# GPduino.net
KiCad netlist of a schematic drawn in EAGLE
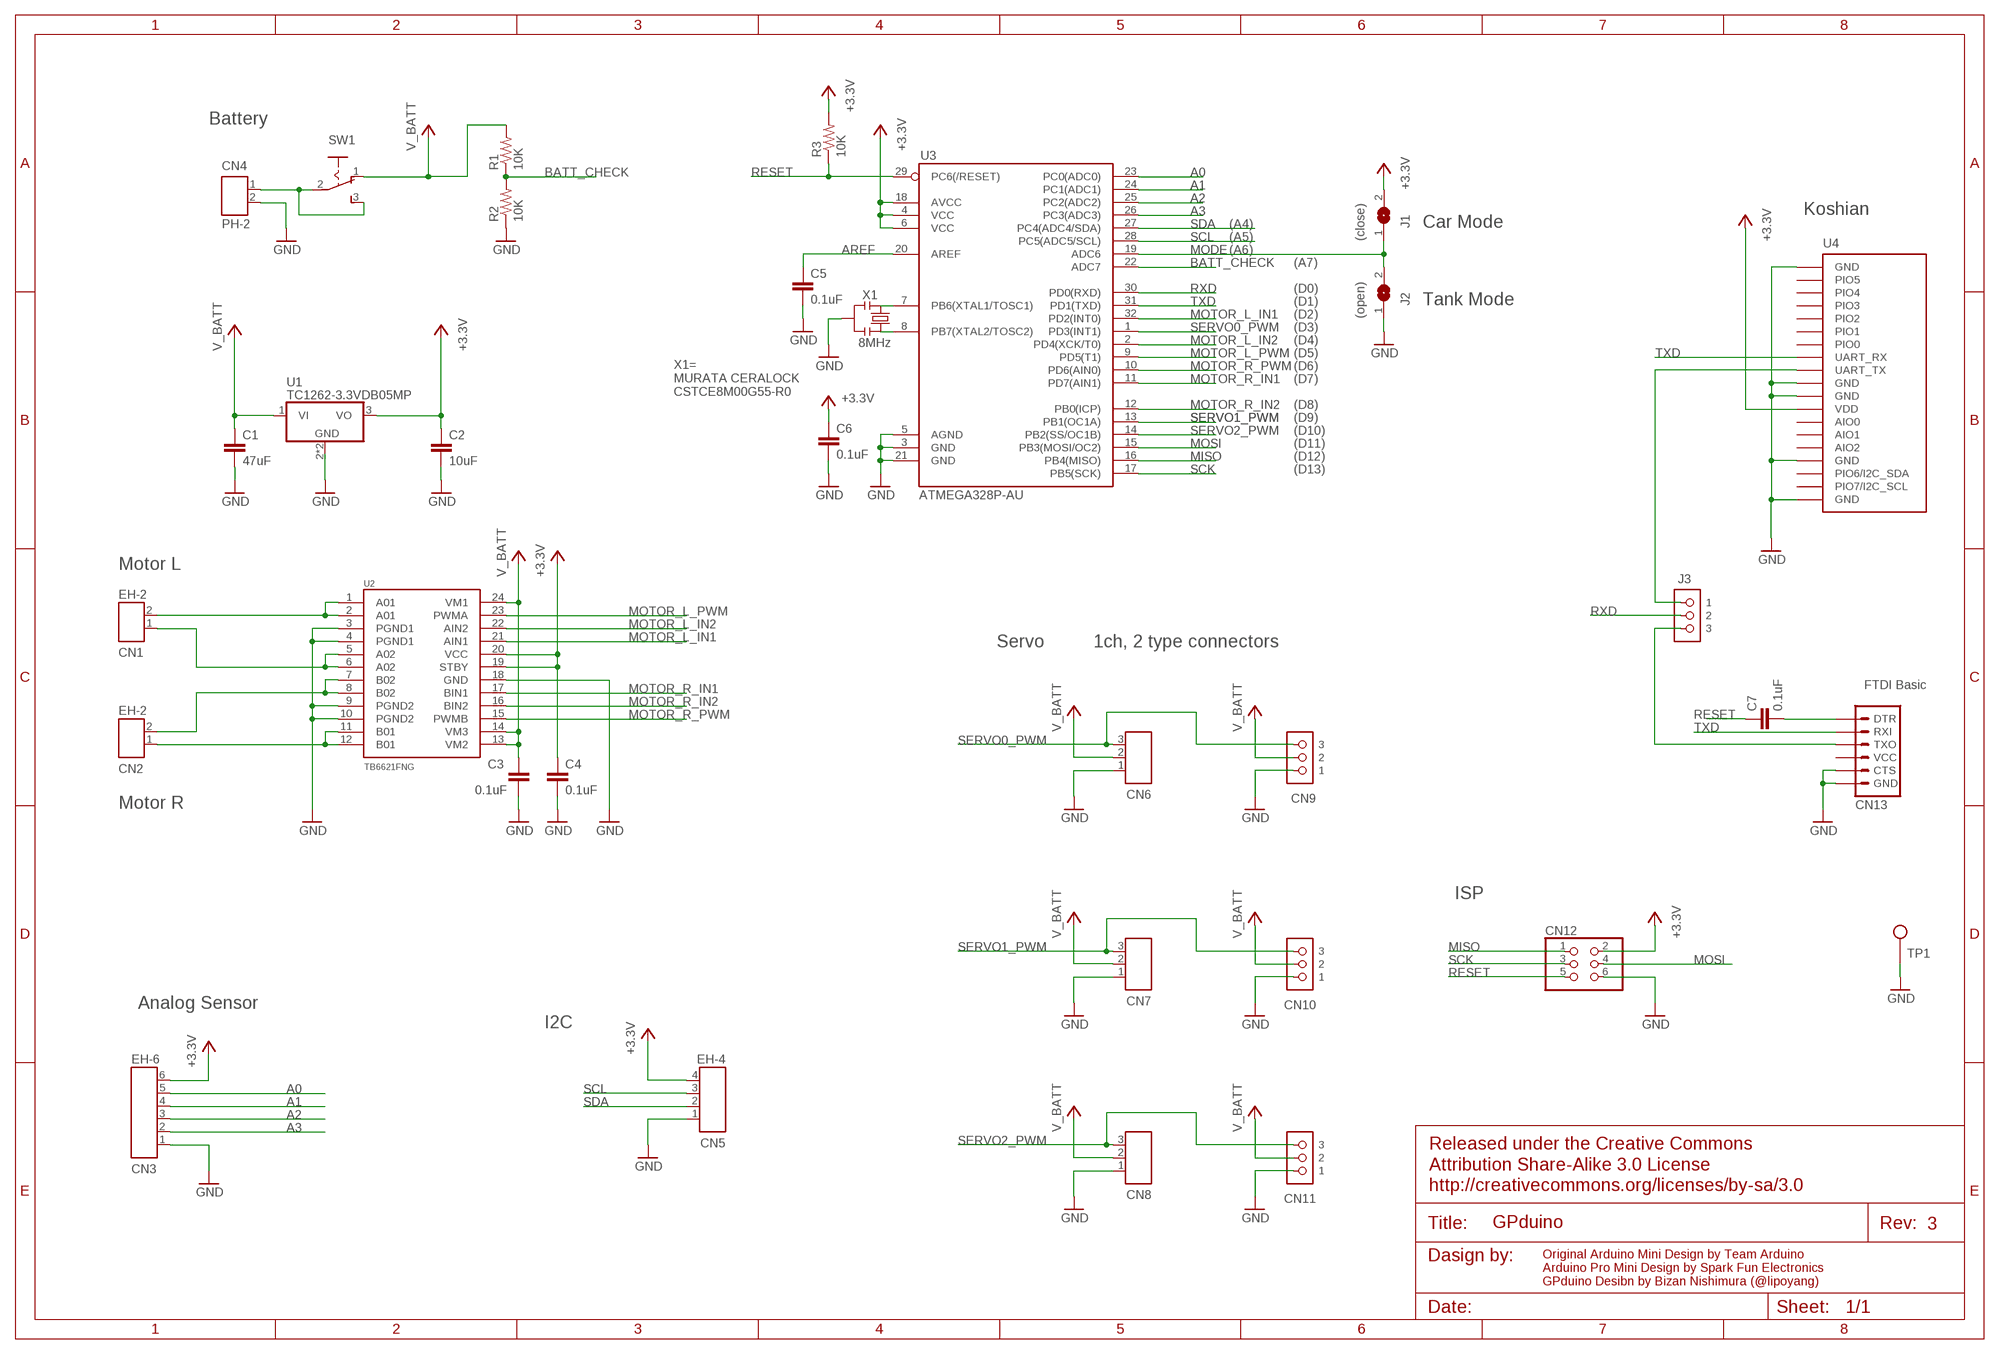
[diagram p0: schematic, sheet 1]

(export (version "E")
  (design (tool "Eeschema 10.0.6"))
  (components
    (comp (ref "C1")
      (value "47uF")
      (footprint "eagle-import:C3216")
      (libsource (lib "eagle-import") (part "C-EUC3216"))
    )
    (comp (ref "C2")
      (value "10uF")
      (footprint "eagle-import:C3216")
      (libsource (lib "eagle-import") (part "C-EUC3216"))
    )
    (comp (ref "C3")
      (value "0.1uF")
      (footprint "eagle-import:C1608")
      (libsource (lib "eagle-import") (part "C-EUC1608"))
    )
    (comp (ref "C4")
      (value "0.1uF")
      (footprint "eagle-import:C1608")
      (libsource (lib "eagle-import") (part "C-EUC1608"))
    )
    (comp (ref "C5")
      (value "0.1uF")
      (footprint "eagle-import:C1608")
      (libsource (lib "eagle-import") (part "C-EUC1608"))
    )
    (comp (ref "C6")
      (value "0.1uF")
      (footprint "eagle-import:C1608")
      (libsource (lib "eagle-import") (part "C-EUC1608"))
    )
    (comp (ref "C7")
      (value "0.1uF")
      (footprint "eagle-import:C1608")
      (libsource (lib "eagle-import") (part "C-EUC1608"))
    )
    (comp (ref "CN1")
      (value "EH-2")
      (footprint "eagle-import:EH-2")
      (libsource (lib "eagle-import") (part "EH-2"))
    )
    (comp (ref "CN2")
      (value "EH-2")
      (footprint "eagle-import:EH-2")
      (libsource (lib "eagle-import") (part "EH-2"))
    )
    (comp (ref "CN3")
      (value "EH-6")
      (footprint "eagle-import:EH-6")
      (libsource (lib "eagle-import") (part "EH-6"))
    )
    (comp (ref "CN4")
      (value "PH-2")
      (footprint "eagle-import:PH-2")
      (libsource (lib "eagle-import") (part "PH-2"))
    )
    (comp (ref "CN5")
      (value "EH-4")
      (footprint "eagle-import:EH-4")
      (libsource (lib "eagle-import") (part "EH-4"))
    )
    (comp (ref "CN6")
      (value "PICOBLADE-3")
      (footprint "eagle-import:PICOBLADE-3")
      (libsource (lib "eagle-import") (part "PICOBLADE-3"))
    )
    (comp (ref "CN7")
      (value "PICOBLADE-3")
      (footprint "eagle-import:PICOBLADE-3")
      (libsource (lib "eagle-import") (part "PICOBLADE-3"))
    )
    (comp (ref "CN8")
      (value "PICOBLADE-3")
      (footprint "eagle-import:PICOBLADE-3")
      (libsource (lib "eagle-import") (part "PICOBLADE-3"))
    )
    (comp (ref "CN9")
      (value "cn6")
      (footprint "eagle-import:CON_RC_SERVO")
      (libsource (lib "eagle-import") (part "PINHD-1X3"))
    )
    (comp (ref "CN10")
      (value "cn6")
      (footprint "eagle-import:CON_RC_SERVO")
      (libsource (lib "eagle-import") (part "PINHD-1X3"))
    )
    (comp (ref "CN11")
      (value "cn6")
      (footprint "eagle-import:CON_RC_SERVO")
      (libsource (lib "eagle-import") (part "PINHD-1X3"))
    )
    (comp (ref "CN12")
      (value "CN9")
      (footprint "eagle-import:2X03")
      (libsource (lib "eagle-import") (part "PINHD-2X3"))
    )
    (comp (ref "CN13")
      (value "FTDI Basic")
      (footprint "eagle-import:1X06")
      (libsource (lib "eagle-import") (part "ARDUINO_SERIAL_PROGRAMPTH"))
    )
    (comp (ref "J1")
      (value "(close)")
      (footprint "eagle-import:SJ")
      (libsource (lib "eagle-import") (part "SJ"))
    )
    (comp (ref "J2")
      (value "(open)")
      (footprint "eagle-import:SJ")
      (libsource (lib "eagle-import") (part "SJ"))
    )
    (comp (ref "J3")
      (value "XX-2")
      (footprint "eagle-import:JUMPER_PIN_1X3")
      (libsource (lib "eagle-import") (part "JUMPER_PIN_1X3"))
    )
    (comp (ref "R1")
      (value "10K")
      (footprint "eagle-import:0603-RES")
      (libsource (lib "eagle-import") (part "RESISTOR0603-RES"))
    )
    (comp (ref "R2")
      (value "10K")
      (footprint "eagle-import:0603-RES")
      (libsource (lib "eagle-import") (part "RESISTOR0603-RES"))
    )
    (comp (ref "R3")
      (value "10K")
      (footprint "eagle-import:0603-RES")
      (libsource (lib "eagle-import") (part "RESISTOR0603-RES"))
    )
    (comp (ref "SW1")
      (value "SW1")
      (footprint "eagle-import:SLIDE-SW")
      (libsource (lib "eagle-import") (part "M251"))
    )
    (comp (ref "TP1")
      (value "TEST_PIN")
      (footprint "eagle-import:TEST_PIN")
      (libsource (lib "eagle-import") (part "TEST_PIN"))
    )
    (comp (ref "U1")
      (value "TC1262-3.3VDB05MP")
      (footprint "eagle-import:SOT223")
      (libsource (lib "eagle-import") (part "TC1262-3.3VDBMP05"))
    )
    (comp (ref "U2")
      (value "TB6621FNG")
      (footprint "eagle-import:SSOP24")
      (libsource (lib "eagle-import") (part "TB6621FNG"))
    )
    (comp (ref "U3")
      (value "ATMEGA328P-AU")
      (footprint "eagle-import:TQFP32-08")
      (libsource (lib "eagle-import") (part "ATMEGA168"))
    )
    (comp (ref "U4")
      (value "KOSHIAN")
      (footprint "eagle-import:KOSHIAN")
      (libsource (lib "eagle-import") (part "KOSHIAN"))
    )
    (comp (ref "X1")
      (value "8MHz")
      (footprint "eagle-import:RESONATOR-SMD-1_1")
      (libsource (lib "eagle-import") (part "RESONATOR1{colon}1"))
    )
  )
  (nets
    (net (code "1") (name "+3.3V") (class "Default")
      (node (ref "C2") (pin "1") (pinfunction "1_1") (pintype "passive"))
      (node (ref "C4") (pin "1") (pinfunction "1_1") (pintype "passive"))
      (node (ref "C6") (pin "1") (pinfunction "1_1") (pintype "passive"))
      (node (ref "CN12") (pin "2") (pinfunction "2_2") (pintype "passive"))
      (node (ref "CN3") (pin "6") (pinfunction "6_6") (pintype "bidirectional"))
      (node (ref "CN5") (pin "4") (pinfunction "4_4") (pintype "bidirectional"))
      (node (ref "J1") (pin "2") (pinfunction "2_2") (pintype "passive"))
      (node (ref "R3") (pin "2") (pinfunction "2_2") (pintype "passive"))
      (node (ref "U1") (pin "3") (pinfunction "VO_3") (pintype "passive"))
      (node (ref "U2") (pin "19") (pinfunction "STBY_19") (pintype "bidirectional"))
      (node (ref "U2") (pin "20") (pinfunction "VCC_20") (pintype "bidirectional"))
      (node (ref "U3") (pin "18") (pinfunction "AVCC_18") (pintype "bidirectional"))
      (node (ref "U3") (pin "4") (pinfunction "VCC_4") (pintype "bidirectional"))
      (node (ref "U3") (pin "6") (pinfunction "VCC_6") (pintype "bidirectional"))
      (node (ref "U4") (pin "12") (pinfunction "VDD_12") (pintype "power_in"))
    )
    (net (code "2") (name "/A0") (class "Default")
      (node (ref "CN3") (pin "5") (pinfunction "5_5") (pintype "bidirectional"))
      (node (ref "U3") (pin "23") (pinfunction "PC0(ADC0)_23") (pintype "bidirectional"))
    )
    (net (code "3") (name "/A1") (class "Default")
      (node (ref "CN3") (pin "4") (pinfunction "4_4") (pintype "bidirectional"))
      (node (ref "U3") (pin "24") (pinfunction "PC1(ADC1)_24") (pintype "bidirectional"))
    )
    (net (code "4") (name "/A2") (class "Default")
      (node (ref "CN3") (pin "3") (pinfunction "3_3") (pintype "bidirectional"))
      (node (ref "U3") (pin "25") (pinfunction "PC2(ADC2)_25") (pintype "bidirectional"))
    )
    (net (code "5") (name "/A3") (class "Default")
      (node (ref "CN3") (pin "2") (pinfunction "2_2") (pintype "bidirectional"))
      (node (ref "U3") (pin "26") (pinfunction "PC3(ADC3)_26") (pintype "bidirectional"))
    )
    (net (code "6") (name "/AREF") (class "Default")
      (node (ref "C5") (pin "1") (pinfunction "1_1") (pintype "passive"))
      (node (ref "U3") (pin "20") (pinfunction "AREF_20") (pintype "bidirectional"))
    )
    (net (code "7") (name "/BATT_CHECK") (class "Default")
      (node (ref "R1") (pin "1") (pinfunction "1_1") (pintype "passive"))
      (node (ref "R2") (pin "2") (pinfunction "2_2") (pintype "passive"))
      (node (ref "U3") (pin "22") (pinfunction "ADC7_22") (pintype "bidirectional"))
    )
    (net (code "8") (name "/MISO") (class "Default")
      (node (ref "CN12") (pin "1") (pinfunction "1_1") (pintype "passive"))
      (node (ref "U3") (pin "16") (pinfunction "PB4(MISO)_16") (pintype "bidirectional"))
    )
    (net (code "9") (name "/MODE") (class "Default")
      (node (ref "J1") (pin "1") (pinfunction "1_1") (pintype "passive"))
      (node (ref "J2") (pin "2") (pinfunction "2_2") (pintype "passive"))
      (node (ref "U3") (pin "19") (pinfunction "ADC6_19") (pintype "bidirectional"))
    )
    (net (code "10") (name "/MOSI") (class "Default")
      (node (ref "CN12") (pin "4") (pinfunction "4_4") (pintype "passive"))
      (node (ref "U3") (pin "15") (pinfunction "PB3(MOSI/OC2)_15") (pintype "bidirectional"))
    )
    (net (code "11") (name "/MOTOR_L_IN1") (class "Default")
      (node (ref "U2") (pin "21") (pinfunction "AIN1_21") (pintype "bidirectional"))
      (node (ref "U3") (pin "32") (pinfunction "PD2(INT0)_32") (pintype "bidirectional"))
    )
    (net (code "12") (name "/MOTOR_L_IN2") (class "Default")
      (node (ref "U2") (pin "22") (pinfunction "AIN2_22") (pintype "bidirectional"))
      (node (ref "U3") (pin "2") (pinfunction "PD4(XCK/T0)_2") (pintype "bidirectional"))
    )
    (net (code "13") (name "/MOTOR_L_PWM") (class "Default")
      (node (ref "U2") (pin "23") (pinfunction "PWMA_23") (pintype "bidirectional"))
      (node (ref "U3") (pin "9") (pinfunction "PD5(T1)_9") (pintype "bidirectional"))
    )
    (net (code "14") (name "/MOTOR_R_IN1") (class "Default")
      (node (ref "U2") (pin "17") (pinfunction "BIN1_17") (pintype "bidirectional"))
      (node (ref "U3") (pin "11") (pinfunction "PD7(AIN1)_11") (pintype "bidirectional"))
    )
    (net (code "15") (name "/MOTOR_R_IN2") (class "Default")
      (node (ref "U2") (pin "16") (pinfunction "BIN2_16") (pintype "bidirectional"))
      (node (ref "U3") (pin "12") (pinfunction "PB0(ICP)_12") (pintype "bidirectional"))
    )
    (net (code "16") (name "/MOTOR_R_PWM") (class "Default")
      (node (ref "U2") (pin "15") (pinfunction "PWMB_15") (pintype "bidirectional"))
      (node (ref "U3") (pin "10") (pinfunction "PD6(AIN0)_10") (pintype "bidirectional"))
    )
    (net (code "17") (name "/RESET") (class "Default")
      (node (ref "C7") (pin "1") (pinfunction "1_1") (pintype "passive"))
      (node (ref "CN12") (pin "5") (pinfunction "5_5") (pintype "passive"))
      (node (ref "R3") (pin "1") (pinfunction "1_1") (pintype "passive"))
      (node (ref "U3") (pin "29") (pinfunction "PC6(/RESET)_29") (pintype "bidirectional"))
    )
    (net (code "18") (name "/RXD") (class "Default")
      (node (ref "J3") (pin "2") (pinfunction "2_2") (pintype "passive"))
      (node (ref "U3") (pin "30") (pinfunction "PD0(RXD)_30") (pintype "bidirectional"))
    )
    (net (code "19") (name "/SCK") (class "Default")
      (node (ref "CN12") (pin "3") (pinfunction "3_3") (pintype "passive"))
      (node (ref "U3") (pin "17") (pinfunction "PB5(SCK)_17") (pintype "bidirectional"))
    )
    (net (code "20") (name "/SCL") (class "Default")
      (node (ref "CN5") (pin "3") (pinfunction "3_3") (pintype "bidirectional"))
      (node (ref "U3") (pin "28") (pinfunction "PC5(ADC5/SCL)_28") (pintype "bidirectional"))
    )
    (net (code "21") (name "/SDA") (class "Default")
      (node (ref "CN5") (pin "2") (pinfunction "2_2") (pintype "bidirectional"))
      (node (ref "U3") (pin "27") (pinfunction "PC4(ADC4/SDA)_27") (pintype "bidirectional"))
    )
    (net (code "22") (name "/SERVO0_PWM") (class "Default")
      (node (ref "CN6") (pin "3") (pinfunction "3_3") (pintype "bidirectional"))
      (node (ref "CN9") (pin "3") (pinfunction "3_3") (pintype "passive"))
      (node (ref "U3") (pin "1") (pinfunction "PD3(INT1)_1") (pintype "bidirectional"))
    )
    (net (code "23") (name "/SERVO1_PWM") (class "Default")
      (node (ref "CN10") (pin "3") (pinfunction "3_3") (pintype "passive"))
      (node (ref "CN7") (pin "3") (pinfunction "3_3") (pintype "bidirectional"))
      (node (ref "U3") (pin "13") (pinfunction "PB1(OC1A)_13") (pintype "bidirectional"))
    )
    (net (code "24") (name "/SERVO2_PWM") (class "Default")
      (node (ref "CN11") (pin "3") (pinfunction "3_3") (pintype "passive"))
      (node (ref "CN8") (pin "3") (pinfunction "3_3") (pintype "bidirectional"))
      (node (ref "U3") (pin "14") (pinfunction "PB2(SS/OC1B)_14") (pintype "bidirectional"))
    )
    (net (code "25") (name "/TXD") (class "Default")
      (node (ref "CN13") (pin "2") (pinfunction "RXI_2") (pintype "passive"))
      (node (ref "U3") (pin "31") (pinfunction "PD1(TXD)_31") (pintype "bidirectional"))
      (node (ref "U4") (pin "8") (pinfunction "UART_RX_8") (pintype "bidirectional"))
      (node (ref "U4") (pin "8@2") (pinfunction "UART_RX_8@2") (pintype "bidirectional"))
    )
    (net (code "26") (name "GND") (class "Default")
      (node (ref "C1") (pin "2") (pinfunction "2_2") (pintype "passive"))
      (node (ref "C2") (pin "2") (pinfunction "2_2") (pintype "passive"))
      (node (ref "C3") (pin "2") (pinfunction "2_2") (pintype "passive"))
      (node (ref "C4") (pin "2") (pinfunction "2_2") (pintype "passive"))
      (node (ref "C5") (pin "2") (pinfunction "2_2") (pintype "passive"))
      (node (ref "C6") (pin "2") (pinfunction "2_2") (pintype "passive"))
      (node (ref "CN10") (pin "1") (pinfunction "1_1") (pintype "passive"))
      (node (ref "CN11") (pin "1") (pinfunction "1_1") (pintype "passive"))
      (node (ref "CN12") (pin "6") (pinfunction "6_6") (pintype "passive"))
      (node (ref "CN13") (pin "5") (pinfunction "CTS_5") (pintype "passive"))
      (node (ref "CN13") (pin "6") (pinfunction "GND_6") (pintype "passive"))
      (node (ref "CN3") (pin "1") (pinfunction "1_1") (pintype "bidirectional"))
      (node (ref "CN4") (pin "2") (pinfunction "2_2") (pintype "bidirectional"))
      (node (ref "CN5") (pin "1") (pinfunction "1_1") (pintype "bidirectional"))
      (node (ref "CN6") (pin "1") (pinfunction "1_1") (pintype "bidirectional"))
      (node (ref "CN7") (pin "1") (pinfunction "1_1") (pintype "bidirectional"))
      (node (ref "CN8") (pin "1") (pinfunction "1_1") (pintype "bidirectional"))
      (node (ref "CN9") (pin "1") (pinfunction "1_1") (pintype "passive"))
      (node (ref "J2") (pin "1") (pinfunction "1_1") (pintype "passive"))
      (node (ref "R2") (pin "1") (pinfunction "1_1") (pintype "passive"))
      (node (ref "TP1") (pin "1") (pinfunction "P$1_1") (pintype "bidirectional"))
      (node (ref "U1") (pin "2") (pinfunction "GND_2") (pintype "passive"))
      (node (ref "U1") (pin "4") (pinfunction "GND_4") (pintype "passive"))
      (node (ref "U2") (pin "10") (pinfunction "PGND2_10") (pintype "bidirectional"))
      (node (ref "U2") (pin "18") (pinfunction "GND_18") (pintype "bidirectional"))
      (node (ref "U2") (pin "3") (pinfunction "PGND1_3") (pintype "bidirectional"))
      (node (ref "U2") (pin "4") (pinfunction "PGND1_4") (pintype "bidirectional"))
      (node (ref "U2") (pin "9") (pinfunction "PGND2_9") (pintype "bidirectional"))
      (node (ref "U3") (pin "21") (pinfunction "GND_21") (pintype "bidirectional"))
      (node (ref "U3") (pin "3") (pinfunction "GND_3") (pintype "bidirectional"))
      (node (ref "U3") (pin "5") (pinfunction "AGND_5") (pintype "bidirectional"))
      (node (ref "U4") (pin "1") (pinfunction "GND_1") (pintype "power_in"))
      (node (ref "U4") (pin "10") (pinfunction "GND_10") (pintype "power_in"))
      (node (ref "U4") (pin "11") (pinfunction "GND_11") (pintype "power_in"))
      (node (ref "U4") (pin "16") (pinfunction "GND_16") (pintype "power_in"))
      (node (ref "U4") (pin "16@2") (pinfunction "GND_16@2") (pintype "power_in"))
      (node (ref "U4") (pin "20") (pinfunction "GND_20") (pintype "power_in"))
      (node (ref "X1") (pin "2") (pinfunction "2_2") (pintype "passive"))
    )
    (net (code "27") (name "Net-(CN1-Pad1)") (class "Default")
      (node (ref "CN1") (pin "1") (pinfunction "1_1") (pintype "bidirectional"))
      (node (ref "U2") (pin "5") (pinfunction "A02_5") (pintype "bidirectional"))
      (node (ref "U2") (pin "6") (pinfunction "A02_6") (pintype "bidirectional"))
    )
    (net (code "28") (name "Net-(CN1-Pad2)") (class "Default")
      (node (ref "CN1") (pin "2") (pinfunction "2_2") (pintype "bidirectional"))
      (node (ref "U2") (pin "1") (pinfunction "A01_1") (pintype "bidirectional"))
      (node (ref "U2") (pin "2") (pinfunction "A01_2") (pintype "bidirectional"))
    )
    (net (code "29") (name "Net-(CN2-Pad1)") (class "Default")
      (node (ref "CN2") (pin "1") (pinfunction "1_1") (pintype "bidirectional"))
      (node (ref "U2") (pin "11") (pinfunction "B01_11") (pintype "bidirectional"))
      (node (ref "U2") (pin "12") (pinfunction "B01_12") (pintype "bidirectional"))
    )
    (net (code "30") (name "Net-(CN2-Pad2)") (class "Default")
      (node (ref "CN2") (pin "2") (pinfunction "2_2") (pintype "bidirectional"))
      (node (ref "U2") (pin "7") (pinfunction "B02_7") (pintype "bidirectional"))
      (node (ref "U2") (pin "8") (pinfunction "B02_8") (pintype "bidirectional"))
    )
    (net (code "31") (name "Net-(CN13-DTR)") (class "Default")
      (node (ref "C7") (pin "2") (pinfunction "2_2") (pintype "passive"))
      (node (ref "CN13") (pin "1") (pinfunction "DTR_1") (pintype "passive"))
    )
    (net (code "32") (name "Net-(CN13-TXO)") (class "Default")
      (node (ref "CN13") (pin "3") (pinfunction "TXO_3") (pintype "passive"))
      (node (ref "J3") (pin "3") (pinfunction "3_3") (pintype "passive"))
    )
    (net (code "33") (name "Net-(SW1-P)") (class "Default")
      (node (ref "CN4") (pin "1") (pinfunction "1_1") (pintype "bidirectional"))
      (node (ref "SW1") (pin "2") (pinfunction "P_2") (pintype "passive"))
      (node (ref "SW1") (pin "3") (pinfunction "S_3") (pintype "passive"))
    )
    (net (code "34") (name "Net-(U3-PB6(XTAL1{slash}TOSC1))") (class "Default")
      (node (ref "U3") (pin "7") (pinfunction "PB6(XTAL1/TOSC1)_7") (pintype "bidirectional"))
      (node (ref "X1") (pin "1") (pinfunction "1_1") (pintype "passive"))
    )
    (net (code "35") (name "Net-(U3-PB7(XTAL2{slash}TOSC2))") (class "Default")
      (node (ref "U3") (pin "8") (pinfunction "PB7(XTAL2/TOSC2)_8") (pintype "bidirectional"))
      (node (ref "X1") (pin "3") (pinfunction "3_3") (pintype "passive"))
    )
    (net (code "36") (name "Net-(U4-UART_TX)") (class "Default")
      (node (ref "J3") (pin "1") (pinfunction "1_1") (pintype "passive"))
      (node (ref "U4") (pin "9") (pinfunction "UART_TX_9") (pintype "bidirectional"))
    )
    (net (code "37") (name "V_BATT") (class "Default")
      (node (ref "C1") (pin "1") (pinfunction "1_1") (pintype "passive"))
      (node (ref "C3") (pin "1") (pinfunction "1_1") (pintype "passive"))
      (node (ref "CN10") (pin "2") (pinfunction "2_2") (pintype "passive"))
      (node (ref "CN11") (pin "2") (pinfunction "2_2") (pintype "passive"))
      (node (ref "CN6") (pin "2") (pinfunction "2_2") (pintype "bidirectional"))
      (node (ref "CN7") (pin "2") (pinfunction "2_2") (pintype "bidirectional"))
      (node (ref "CN8") (pin "2") (pinfunction "2_2") (pintype "bidirectional"))
      (node (ref "CN9") (pin "2") (pinfunction "2_2") (pintype "passive"))
      (node (ref "R1") (pin "2") (pinfunction "2_2") (pintype "passive"))
      (node (ref "SW1") (pin "1") (pinfunction "O_1") (pintype "passive"))
      (node (ref "U1") (pin "1") (pinfunction "VI_1") (pintype "input"))
      (node (ref "U2") (pin "13") (pinfunction "VM2_13") (pintype "bidirectional"))
      (node (ref "U2") (pin "14") (pinfunction "VM3_14") (pintype "bidirectional"))
      (node (ref "U2") (pin "24") (pinfunction "VM1_24") (pintype "bidirectional"))
    )
    (net (code "38") (name "unconnected-(CN13-VCC-Pad4)") (class "Default")
      (node (ref "CN13") (pin "4") (pinfunction "VCC_4") (pintype "passive"))
    )
    (net (code "39") (name "unconnected-(U4-AIO0-Pad13)") (class "Default")
      (node (ref "U4") (pin "13") (pinfunction "AIO0_13") (pintype "bidirectional"))
    )
    (net (code "40") (name "unconnected-(U4-AIO1-Pad14)") (class "Default")
      (node (ref "U4") (pin "14") (pinfunction "AIO1_14") (pintype "bidirectional"))
    )
    (net (code "41") (name "unconnected-(U4-AIO2-Pad15)") (class "Default")
      (node (ref "U4") (pin "15") (pinfunction "AIO2_15") (pintype "bidirectional"))
    )
    (net (code "42") (name "unconnected-(U4-PIO0-Pad7)") (class "Default")
      (node (ref "U4") (pin "7") (pinfunction "PIO0_7") (pintype "bidirectional"))
    )
    (net (code "43") (name "unconnected-(U4-PIO1-Pad6)") (class "Default")
      (node (ref "U4") (pin "6") (pinfunction "PIO1_6") (pintype "bidirectional"))
    )
    (net (code "44") (name "unconnected-(U4-PIO2-Pad5)") (class "Default")
      (node (ref "U4") (pin "5") (pinfunction "PIO2_5") (pintype "bidirectional"))
    )
    (net (code "45") (name "unconnected-(U4-PIO3-Pad4)") (class "Default")
      (node (ref "U4") (pin "4") (pinfunction "PIO3_4") (pintype "bidirectional"))
    )
    (net (code "46") (name "unconnected-(U4-PIO4-Pad3)") (class "Default")
      (node (ref "U4") (pin "3") (pinfunction "PIO4_3") (pintype "bidirectional"))
    )
    (net (code "47") (name "unconnected-(U4-PIO5-Pad2)") (class "Default")
      (node (ref "U4") (pin "2") (pinfunction "PIO5_2") (pintype "bidirectional"))
    )
    (net (code "48") (name "unconnected-(U4-PIO6{slash}I2C_SDA-Pad17)") (class "Default")
      (node (ref "U4") (pin "17") (pinfunction "PIO6/I2C_SDA_17") (pintype "bidirectional"))
    )
    (net (code "49") (name "unconnected-(U4-PIO7{slash}I2C_SCL-Pad18)") (class "Default")
      (node (ref "U4") (pin "18") (pinfunction "PIO7/I2C_SCL_18") (pintype "bidirectional"))
    )
  )
)
